# easyeda-schematic.net
KiCad netlist of a schematic drawn in EasyEDA
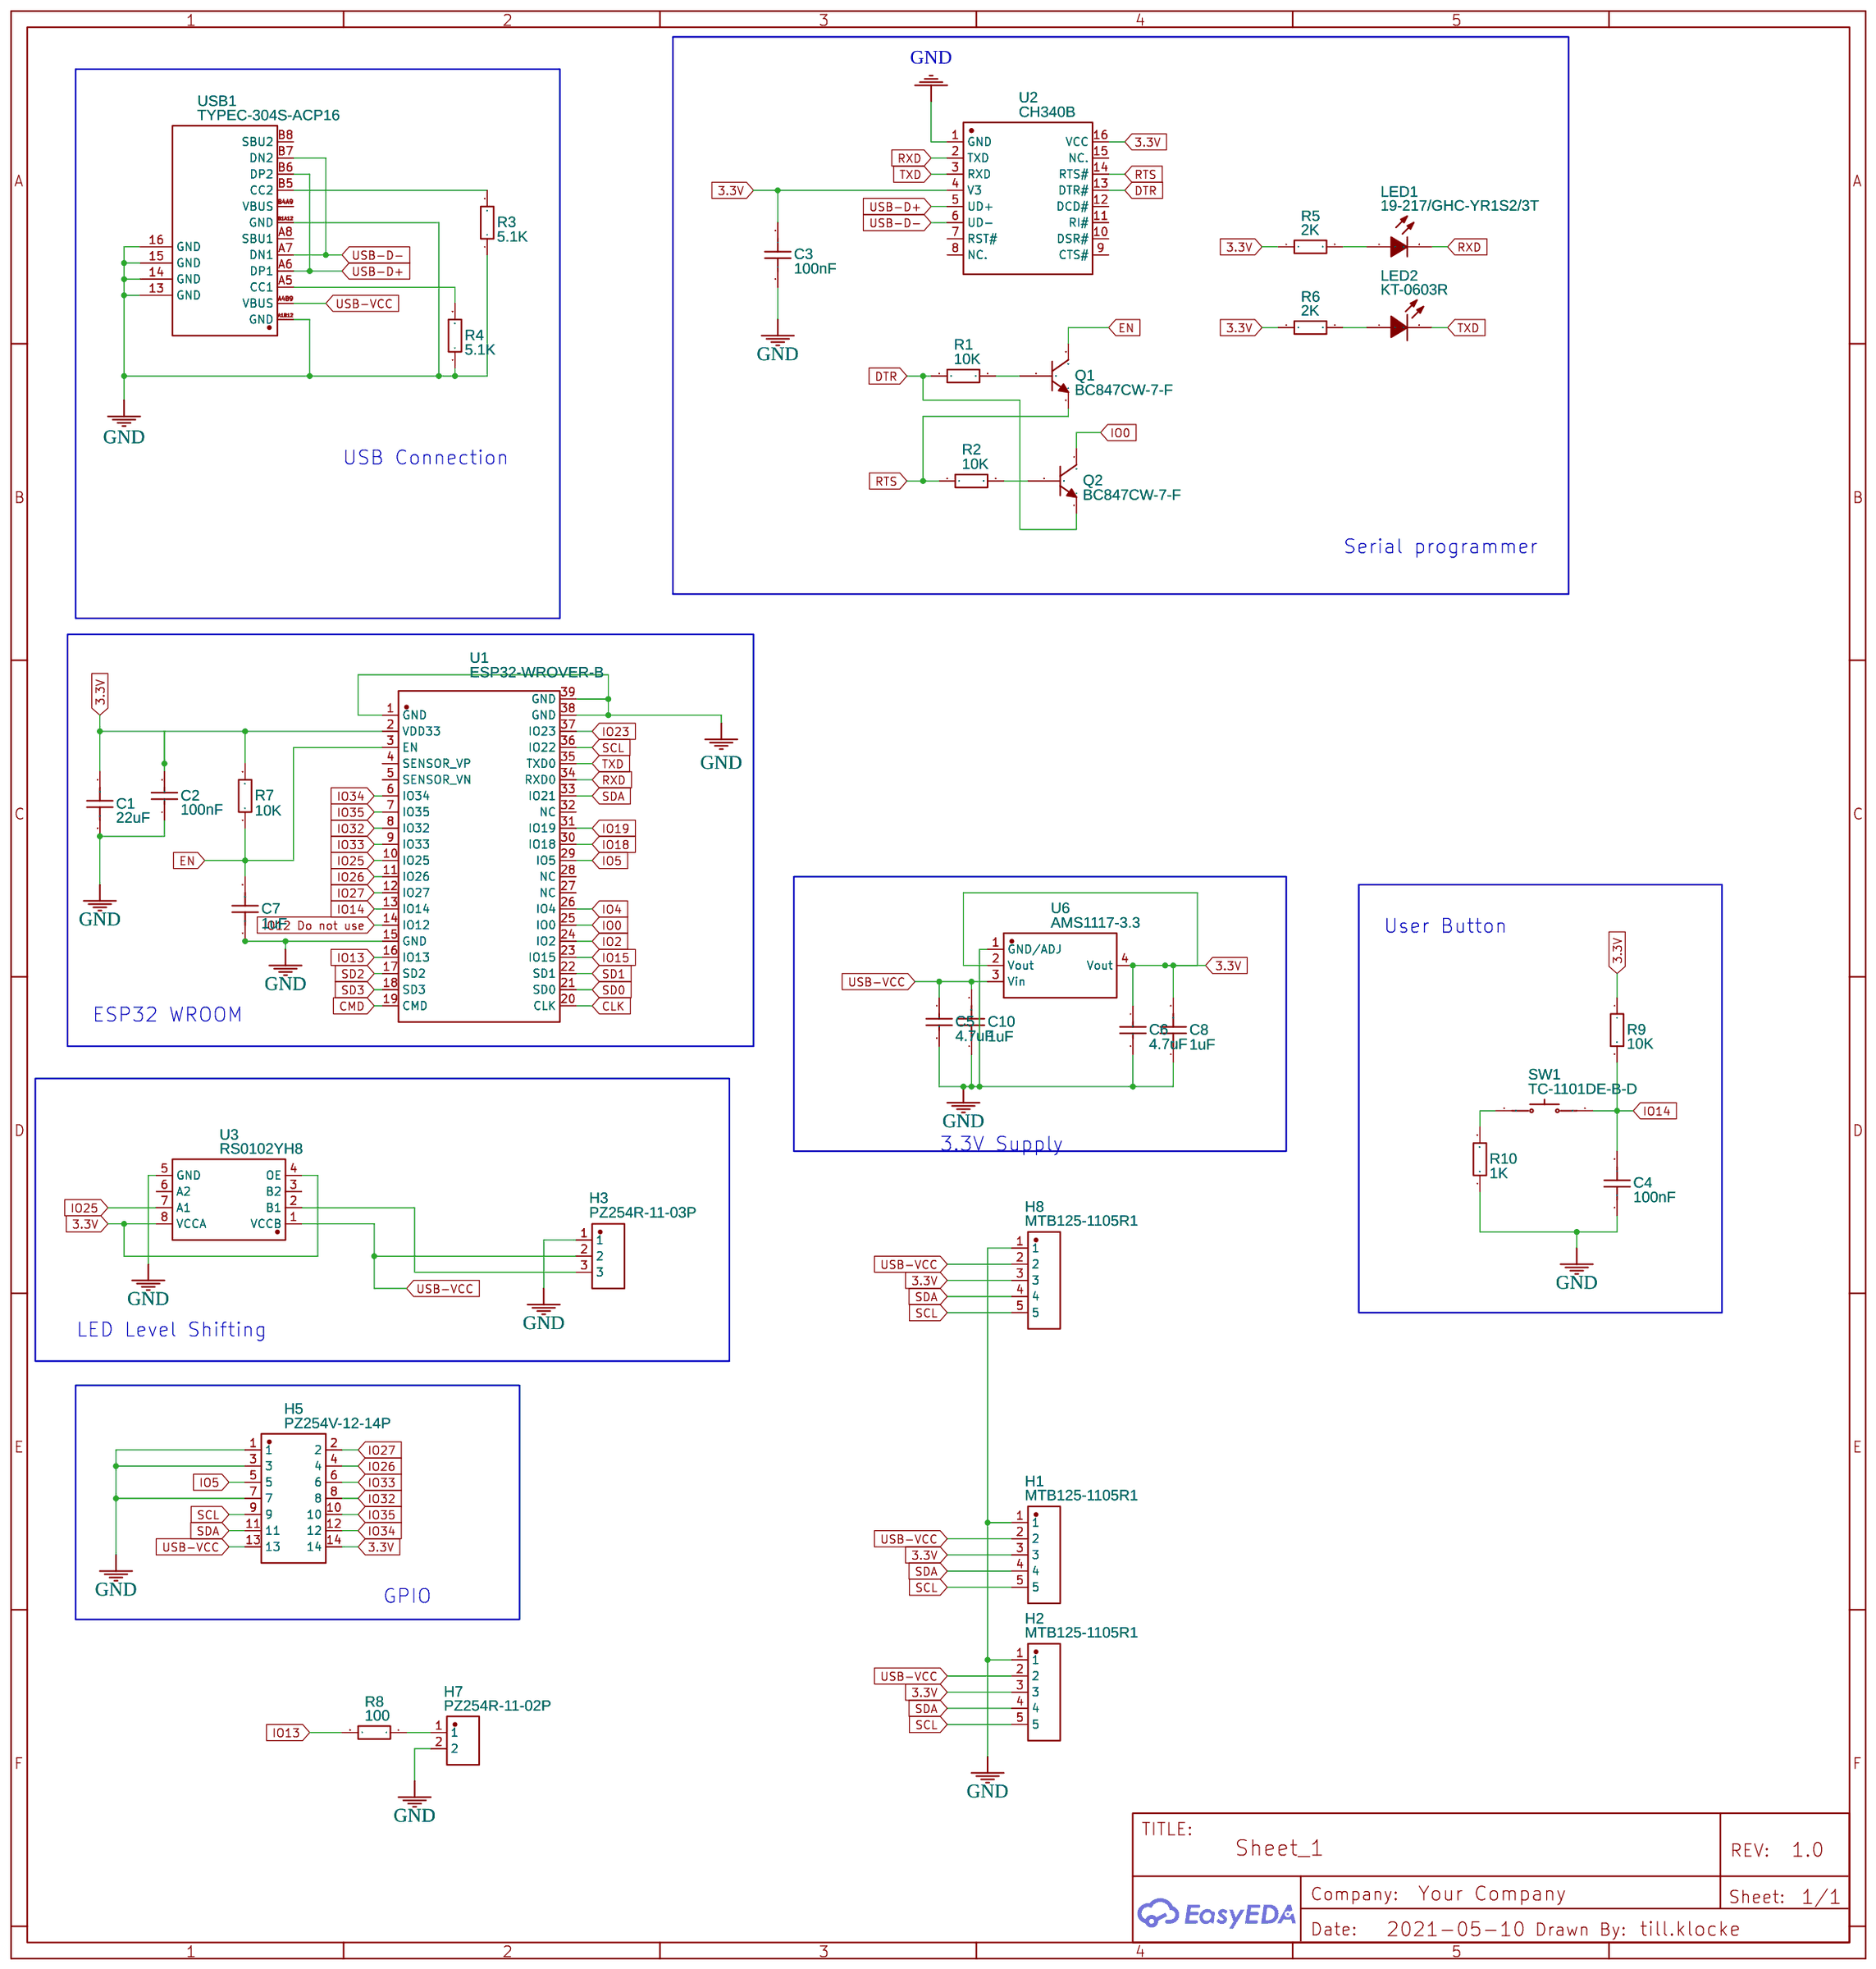
[diagram p0: schematic sheet]

(export (version "E")
  (design (tool "Eeschema 10.0.6"))
  (components
    (comp (ref "C1")
      (value "22uF")
      (fields
        (field (name "BOM_Manufacturer Part") "CL10A226MQ8NRNC")
        (field (name "BOM_Supplier Part") "C59461")
      )
      (libsource (lib "") (part "CL10A226MQ8NRNC"))
    )
    (comp (ref "C2")
      (value "100nF")
      (fields
        (field (name "BOM_Manufacturer Part") "CL05B104KO5NNNC")
        (field (name "BOM_Supplier Part") "C1525")
      )
      (libsource (lib "") (part "CL05B104KO5NNNC"))
    )
    (comp (ref "C3")
      (value "100nF")
      (fields
        (field (name "BOM_Manufacturer Part") "CC0603KRX7R9BB104")
        (field (name "BOM_Supplier Part") "C14663")
      )
      (libsource (lib "") (part "CC0603KRX7R9BB104"))
    )
    (comp (ref "C4")
      (value "100nF")
      (fields
        (field (name "BOM_Manufacturer Part") "CC0603KRX7R9BB104")
        (field (name "BOM_Supplier Part") "C14663")
      )
      (libsource (lib "") (part "CC0603KRX7R9BB104"))
    )
    (comp (ref "C5")
      (value "4.7uF")
      (fields
        (field (name "BOM_Manufacturer Part") "CL05A475MP5NRNC")
        (field (name "BOM_Supplier Part") "C23733")
      )
      (libsource (lib "") (part "CL05A475MP5NRNC"))
    )
    (comp (ref "C6")
      (value "4.7uF")
      (fields
        (field (name "BOM_Manufacturer Part") "CL05A475MP5NRNC")
        (field (name "BOM_Supplier Part") "C23733")
      )
      (libsource (lib "") (part "CL05A475MP5NRNC"))
    )
    (comp (ref "C7")
      (value "1uF")
      (fields
        (field (name "BOM_Manufacturer Part") "CL05A105KA5NQNC")
        (field (name "BOM_Supplier Part") "C52923")
      )
      (libsource (lib "") (part "CL05A105KA5NQNC"))
    )
    (comp (ref "C8")
      (value "1uF")
      (fields
        (field (name "BOM_Manufacturer Part") "CL05A105KA5NQNC")
        (field (name "BOM_Supplier Part") "C52923")
      )
      (libsource (lib "") (part "CL05A105KA5NQNC"))
    )
    (comp (ref "C10")
      (value "1uF")
      (fields
        (field (name "BOM_Manufacturer Part") "CL05A105KA5NQNC")
        (field (name "BOM_Supplier Part") "C52923")
      )
      (libsource (lib "") (part "CL05A105KA5NQNC"))
    )
    (comp (ref "H1")
      (value "MTB125-1105R1")
      (fields (field (name "BOM_Supplier Part") "C376123"))
      (libsource (lib "") (part "MTB125-1105R1"))
    )
    (comp (ref "H2")
      (value "MTB125-1105R1")
      (fields (field (name "BOM_Supplier Part") "C376123"))
      (libsource (lib "") (part "MTB125-1105R1"))
    )
    (comp (ref "H3")
      (value "PZ254R-11-03P")
      (fields (field (name "BOM_Supplier Part") "C492411"))
      (libsource (lib "") (part "PZ254R-11-03P"))
    )
    (comp (ref "H5")
      (value "PZ254V-12-14P")
      (fields (field (name "BOM_Supplier Part") "C492424"))
      (libsource (lib "") (part "PZ254V-12-14P"))
    )
    (comp (ref "H7")
      (value "PZ254R-11-02P")
      (fields (field (name "BOM_Supplier Part") "C492410"))
      (libsource (lib "") (part "PZ254R-11-02P"))
    )
    (comp (ref "H8")
      (value "MTB125-1105R1")
      (fields (field (name "BOM_Supplier Part") "C376123"))
      (libsource (lib "") (part "MTB125-1105R1"))
    )
    (comp (ref "LED1")
      (value "19-217/GHC-YR1S2/3T")
      (fields (field (name "BOM_Supplier Part") "C72043"))
      (libsource (lib "") (part "19-217/GHC-YR1S2/3T"))
    )
    (comp (ref "LED2")
      (value "KT-0603R")
      (fields (field (name "BOM_Supplier Part") "C2286"))
      (libsource (lib "") (part "KT-0603R"))
    )
    (comp (ref "Q1")
      (value "BC847CW-7-F")
      (fields (field (name "BOM_Supplier Part") "C151600"))
      (libsource (lib "") (part "BC847CW-7-F"))
    )
    (comp (ref "Q2")
      (value "BC847CW-7-F")
      (fields (field (name "BOM_Supplier Part") "C151600"))
      (libsource (lib "") (part "BC847CW-7-F"))
    )
    (comp (ref "R1")
      (value "10K")
      (fields
        (field (name "BOM_Manufacturer Part") "0402WGF1002TCE")
        (field (name "BOM_Supplier Part") "C25744")
      )
      (libsource (lib "") (part "0402WGF1002TCE"))
    )
    (comp (ref "R2")
      (value "10K")
      (fields
        (field (name "BOM_Manufacturer Part") "0402WGF1002TCE")
        (field (name "BOM_Supplier Part") "C25744")
      )
      (libsource (lib "") (part "0402WGF1002TCE"))
    )
    (comp (ref "R3")
      (value "5.1K")
      (fields
        (field (name "BOM_Manufacturer Part") "0805W8F5101T5E")
        (field (name "BOM_Supplier Part") "C27834")
      )
      (libsource (lib "") (part "0805W8F5101T5E"))
    )
    (comp (ref "R4")
      (value "5.1K")
      (fields
        (field (name "BOM_Manufacturer Part") "0805W8F5101T5E")
        (field (name "BOM_Supplier Part") "C27834")
      )
      (libsource (lib "") (part "0805W8F5101T5E"))
    )
    (comp (ref "R5")
      (value "2K")
      (fields
        (field (name "BOM_Manufacturer Part") "0402WGJ0202TCE")
        (field (name "BOM_Supplier Part") "C25552")
      )
      (libsource (lib "") (part "0402WGJ0202TCE"))
    )
    (comp (ref "R6")
      (value "2K")
      (fields
        (field (name "BOM_Manufacturer Part") "0402WGJ0202TCE")
        (field (name "BOM_Supplier Part") "C25552")
      )
      (libsource (lib "") (part "0402WGJ0202TCE"))
    )
    (comp (ref "R7")
      (value "10K")
      (fields
        (field (name "BOM_Manufacturer Part") "0402WGF1002TCE")
        (field (name "BOM_Supplier Part") "C25744")
      )
      (libsource (lib "") (part "0402WGF1002TCE_1"))
    )
    (comp (ref "R8")
      (value "100")
      (fields
        (field (name "BOM_Manufacturer Part") "RC0402FR-07100RL")
        (field (name "BOM_Supplier Part") "C106232")
      )
      (libsource (lib "") (part "RC0402FR-07100RL"))
    )
    (comp (ref "R9")
      (value "10K")
      (fields
        (field (name "BOM_Manufacturer Part") "0402WGF1002TCE")
        (field (name "BOM_Supplier Part") "C25744")
      )
      (libsource (lib "") (part "0402WGF1002TCE_2"))
    )
    (comp (ref "R10")
      (value "1K")
      (fields
        (field (name "BOM_Manufacturer Part") "0402WGF1001TCE")
        (field (name "BOM_Supplier Part") "C11702")
      )
      (libsource (lib "") (part "0402WGF1001TCE"))
    )
    (comp (ref "SW1")
      (value "TC-1101DE-B-D")
      (fields (field (name "BOM_Supplier Part") "C561494"))
      (libsource (lib "") (part "TC-1101DE-B-D"))
    )
    (comp (ref "U1")
      (value "ESP32-WROVER-B")
      (fields (field (name "BOM_Supplier Part") "C503591"))
      (libsource (lib "") (part "ESP32-WROVER-B"))
    )
    (comp (ref "U2")
      (value "CH340B")
      (fields (field (name "BOM_Supplier Part") "C81010"))
      (libsource (lib "") (part "CH340B"))
    )
    (comp (ref "U3")
      (value "RS0102YH8")
      (fields (field (name "BOM_Supplier Part") "C783414"))
      (libsource (lib "") (part "RS0102YH8"))
    )
    (comp (ref "U6")
      (value "AMS1117-3.3")
      (fields (field (name "BOM_Supplier Part") "C6186"))
      (libsource (lib "") (part "AMS1117-3.3"))
    )
    (comp (ref "USB1")
      (value "TYPEC-304S-ACP16")
      (fields (field (name "BOM_Supplier Part") "C720630"))
      (libsource (lib "") (part "TYPEC-304S-ACP16"))
    )
  )
  (nets
    (net (code "1") (name "3.3V") (class "Default")
      (node (ref "C1") (pin "1") (pinfunction "1_1") (pintype "unspecified"))
      (node (ref "C2") (pin "2") (pinfunction "2_2") (pintype "input"))
      (node (ref "C3") (pin "2") (pinfunction "2_2") (pintype "unspecified"))
      (node (ref "C6") (pin "1") (pinfunction "1_1") (pintype "input"))
      (node (ref "C8") (pin "2") (pinfunction "2_2") (pintype "unspecified"))
      (node (ref "H1") (pin "3") (pinfunction "3_3") (pintype "unspecified"))
      (node (ref "H2") (pin "3") (pinfunction "3_3") (pintype "unspecified"))
      (node (ref "H5") (pin "14") (pinfunction "14_14") (pintype "unspecified"))
      (node (ref "H8") (pin "3") (pinfunction "3_3") (pintype "unspecified"))
      (node (ref "R5") (pin "1") (pinfunction "1_1") (pintype "input"))
      (node (ref "R6") (pin "1") (pinfunction "1_1") (pintype "input"))
      (node (ref "R7") (pin "2") (pinfunction "2_2") (pintype "input"))
      (node (ref "R9") (pin "1") (pinfunction "1_1") (pintype "input"))
      (node (ref "U1") (pin "2") (pinfunction "VDD33_2") (pintype "unspecified"))
      (node (ref "U2") (pin "16") (pinfunction "VCC_16") (pintype "unspecified"))
      (node (ref "U2") (pin "4") (pinfunction "V3_4") (pintype "unspecified"))
      (node (ref "U3") (pin "4") (pinfunction "OE_4") (pintype "unspecified"))
      (node (ref "U3") (pin "8") (pinfunction "VCCA_8") (pintype "unspecified"))
      (node (ref "U6") (pin "2") (pinfunction "Vout_2") (pintype "unspecified"))
      (node (ref "U6") (pin "4") (pinfunction "Vout_4") (pintype "unspecified"))
    )
    (net (code "2") (name "CLK") (class "Default")
      (node (ref "U1") (pin "20") (pinfunction "CLK_20") (pintype "unspecified"))
    )
    (net (code "3") (name "CMD") (class "Default")
      (node (ref "U1") (pin "19") (pinfunction "CMD_19") (pintype "unspecified"))
    )
    (net (code "4") (name "DTR") (class "Default")
      (node (ref "Q2") (pin "2") (pinfunction "E_2") (pintype "unspecified"))
      (node (ref "R1") (pin "1") (pinfunction "1_1") (pintype "input"))
      (node (ref "U2") (pin "13") (pinfunction "DTR#_13") (pintype "unspecified"))
    )
    (net (code "5") (name "EN") (class "Default")
      (node (ref "C7") (pin "2") (pinfunction "2_2") (pintype "unspecified"))
      (node (ref "Q1") (pin "3") (pinfunction "C_3") (pintype "unspecified"))
      (node (ref "R7") (pin "1") (pinfunction "1_1") (pintype "input"))
      (node (ref "U1") (pin "3") (pinfunction "EN_3") (pintype "unspecified"))
    )
    (net (code "6") (name "GND") (class "Default")
      (node (ref "C1") (pin "2") (pinfunction "2_2") (pintype "unspecified"))
      (node (ref "C10") (pin "1") (pinfunction "1_1") (pintype "unspecified"))
      (node (ref "C2") (pin "1") (pinfunction "1_1") (pintype "input"))
      (node (ref "C3") (pin "1") (pinfunction "1_1") (pintype "unspecified"))
      (node (ref "C4") (pin "1") (pinfunction "1_1") (pintype "unspecified"))
      (node (ref "C5") (pin "2") (pinfunction "2_2") (pintype "input"))
      (node (ref "C6") (pin "2") (pinfunction "2_2") (pintype "input"))
      (node (ref "C7") (pin "1") (pinfunction "1_1") (pintype "unspecified"))
      (node (ref "C8") (pin "1") (pinfunction "1_1") (pintype "unspecified"))
      (node (ref "H1") (pin "1") (pinfunction "1_1") (pintype "unspecified"))
      (node (ref "H2") (pin "1") (pinfunction "1_1") (pintype "unspecified"))
      (node (ref "H3") (pin "1") (pinfunction "1_1") (pintype "unspecified"))
      (node (ref "H5") (pin "1") (pinfunction "1_1") (pintype "unspecified"))
      (node (ref "H5") (pin "3") (pinfunction "3_3") (pintype "unspecified"))
      (node (ref "H5") (pin "7") (pinfunction "7_7") (pintype "unspecified"))
      (node (ref "H7") (pin "2") (pinfunction "2_2") (pintype "unspecified"))
      (node (ref "H8") (pin "1") (pinfunction "1_1") (pintype "unspecified"))
      (node (ref "R10") (pin "1") (pinfunction "1_1") (pintype "input"))
      (node (ref "R3") (pin "1") (pinfunction "1_1") (pintype "input"))
      (node (ref "R4") (pin "1") (pinfunction "1_1") (pintype "input"))
      (node (ref "U1") (pin "1") (pinfunction "GND_1") (pintype "unspecified"))
      (node (ref "U1") (pin "15") (pinfunction "GND_15") (pintype "unspecified"))
      (node (ref "U1") (pin "38") (pinfunction "GND_38") (pintype "unspecified"))
      (node (ref "U1") (pin "39") (pinfunction "GND_39") (pintype "unspecified"))
      (node (ref "U2") (pin "1") (pinfunction "GND_1") (pintype "unspecified"))
      (node (ref "U3") (pin "5") (pinfunction "GND_5") (pintype "unspecified"))
      (node (ref "U6") (pin "1") (pinfunction "GND/ADJ_1") (pintype "unspecified"))
      (node (ref "USB1") (pin "13") (pinfunction "GND_13") (pintype "unspecified"))
      (node (ref "USB1") (pin "14") (pinfunction "GND_14") (pintype "unspecified"))
      (node (ref "USB1") (pin "15") (pinfunction "GND_15") (pintype "unspecified"))
      (node (ref "USB1") (pin "16") (pinfunction "GND_16") (pintype "unspecified"))
      (node (ref "USB1") (pin "A1B12") (pinfunction "GND_A1B12") (pintype "unspecified"))
      (node (ref "USB1") (pin "B1A12") (pinfunction "GND_B1A12") (pintype "unspecified"))
    )
    (net (code "7") (name "IO0") (class "Default")
      (node (ref "Q2") (pin "3") (pinfunction "C_3") (pintype "unspecified"))
      (node (ref "U1") (pin "25") (pinfunction "IO0_25") (pintype "unspecified"))
    )
    (net (code "8") (name "IO2") (class "Default")
      (node (ref "U1") (pin "24") (pinfunction "IO2_24") (pintype "unspecified"))
    )
    (net (code "9") (name "IO4") (class "Default")
      (node (ref "U1") (pin "26") (pinfunction "IO4_26") (pintype "unspecified"))
    )
    (net (code "10") (name "IO5") (class "Default")
      (node (ref "H5") (pin "5") (pinfunction "5_5") (pintype "unspecified"))
      (node (ref "U1") (pin "29") (pinfunction "IO5_29") (pintype "unspecified"))
    )
    (net (code "11") (name "IO12 Do not use") (class "Default")
      (node (ref "U1") (pin "14") (pinfunction "IO12_14") (pintype "unspecified"))
    )
    (net (code "12") (name "IO13") (class "Default")
      (node (ref "R8") (pin "2") (pinfunction "2_2") (pintype "input"))
      (node (ref "U1") (pin "16") (pinfunction "IO13_16") (pintype "unspecified"))
    )
    (net (code "13") (name "IO14") (class "Default")
      (node (ref "C4") (pin "2") (pinfunction "2_2") (pintype "unspecified"))
      (node (ref "R9") (pin "2") (pinfunction "2_2") (pintype "input"))
      (node (ref "SW1") (pin "2") (pinfunction "2_2") (pintype "input"))
      (node (ref "U1") (pin "13") (pinfunction "IO14_13") (pintype "unspecified"))
    )
    (net (code "14") (name "IO15") (class "Default")
      (node (ref "U1") (pin "23") (pinfunction "IO15_23") (pintype "unspecified"))
    )
    (net (code "15") (name "IO18") (class "Default")
      (node (ref "U1") (pin "30") (pinfunction "IO18_30") (pintype "unspecified"))
    )
    (net (code "16") (name "IO19") (class "Default")
      (node (ref "U1") (pin "31") (pinfunction "IO19_31") (pintype "unspecified"))
    )
    (net (code "17") (name "IO23") (class "Default")
      (node (ref "U1") (pin "37") (pinfunction "IO23_37") (pintype "unspecified"))
    )
    (net (code "18") (name "IO25") (class "Default")
      (node (ref "U1") (pin "10") (pinfunction "IO25_10") (pintype "unspecified"))
      (node (ref "U3") (pin "7") (pinfunction "A1_7") (pintype "unspecified"))
    )
    (net (code "19") (name "IO26") (class "Default")
      (node (ref "H5") (pin "4") (pinfunction "4_4") (pintype "unspecified"))
      (node (ref "U1") (pin "11") (pinfunction "IO26_11") (pintype "unspecified"))
    )
    (net (code "20") (name "IO27") (class "Default")
      (node (ref "H5") (pin "2") (pinfunction "2_2") (pintype "unspecified"))
      (node (ref "U1") (pin "12") (pinfunction "IO27_12") (pintype "unspecified"))
    )
    (net (code "21") (name "IO32") (class "Default")
      (node (ref "H5") (pin "8") (pinfunction "8_8") (pintype "unspecified"))
      (node (ref "U1") (pin "8") (pinfunction "IO32_8") (pintype "unspecified"))
    )
    (net (code "22") (name "IO33") (class "Default")
      (node (ref "H5") (pin "6") (pinfunction "6_6") (pintype "unspecified"))
      (node (ref "U1") (pin "9") (pinfunction "IO33_9") (pintype "unspecified"))
    )
    (net (code "23") (name "IO34") (class "Default")
      (node (ref "H5") (pin "12") (pinfunction "12_12") (pintype "unspecified"))
      (node (ref "U1") (pin "6") (pinfunction "IO34_6") (pintype "unspecified"))
    )
    (net (code "24") (name "IO35") (class "Default")
      (node (ref "H5") (pin "10") (pinfunction "10_10") (pintype "unspecified"))
      (node (ref "U1") (pin "7") (pinfunction "IO35_7") (pintype "unspecified"))
    )
    (net (code "25") (name "Net-(H7-Pad1)") (class "Default")
      (node (ref "H7") (pin "1") (pinfunction "1_1") (pintype "unspecified"))
      (node (ref "R8") (pin "1") (pinfunction "1_1") (pintype "input"))
    )
    (net (code "26") (name "Net-(LED1-A)") (class "Default")
      (node (ref "LED1") (pin "1") (pinfunction "A_1") (pintype "input"))
      (node (ref "R5") (pin "2") (pinfunction "2_2") (pintype "input"))
    )
    (net (code "27") (name "Net-(LED2-A)") (class "Default")
      (node (ref "LED2") (pin "1") (pinfunction "A_1") (pintype "unspecified"))
      (node (ref "R6") (pin "2") (pinfunction "2_2") (pintype "input"))
    )
    (net (code "28") (name "Net-(Q1-B)") (class "Default")
      (node (ref "Q1") (pin "1") (pinfunction "B_1") (pintype "unspecified"))
      (node (ref "R1") (pin "2") (pinfunction "2_2") (pintype "input"))
    )
    (net (code "29") (name "Net-(Q2-B)") (class "Default")
      (node (ref "Q2") (pin "1") (pinfunction "B_1") (pintype "unspecified"))
      (node (ref "R2") (pin "2") (pinfunction "2_2") (pintype "input"))
    )
    (net (code "30") (name "Net-(R10-Pad2)") (class "Default")
      (node (ref "R10") (pin "2") (pinfunction "2_2") (pintype "input"))
      (node (ref "SW1") (pin "1") (pinfunction "1_1") (pintype "input"))
    )
    (net (code "31") (name "Net-(U3-B1)") (class "Default")
      (node (ref "H3") (pin "3") (pinfunction "3_3") (pintype "unspecified"))
      (node (ref "U3") (pin "2") (pinfunction "B1_2") (pintype "unspecified"))
    )
    (net (code "32") (name "Net-(USB1-CC1)") (class "Default")
      (node (ref "R4") (pin "2") (pinfunction "2_2") (pintype "input"))
      (node (ref "USB1") (pin "A5") (pinfunction "CC1_A5") (pintype "unspecified"))
    )
    (net (code "33") (name "Net-(USB1-CC2)") (class "Default")
      (node (ref "R3") (pin "2") (pinfunction "2_2") (pintype "input"))
      (node (ref "USB1") (pin "B5") (pinfunction "CC2_B5") (pintype "unspecified"))
    )
    (net (code "34") (name "RTS") (class "Default")
      (node (ref "Q1") (pin "2") (pinfunction "E_2") (pintype "unspecified"))
      (node (ref "R2") (pin "1") (pinfunction "1_1") (pintype "input"))
      (node (ref "U2") (pin "14") (pinfunction "RTS#_14") (pintype "unspecified"))
    )
    (net (code "35") (name "RXD") (class "Default")
      (node (ref "LED1") (pin "2") (pinfunction "C_2") (pintype "input"))
      (node (ref "U1") (pin "34") (pinfunction "RXD0_34") (pintype "unspecified"))
      (node (ref "U2") (pin "2") (pinfunction "TXD_2") (pintype "unspecified"))
    )
    (net (code "36") (name "SCL") (class "Default")
      (node (ref "H1") (pin "5") (pinfunction "5_5") (pintype "unspecified"))
      (node (ref "H2") (pin "5") (pinfunction "5_5") (pintype "unspecified"))
      (node (ref "H5") (pin "9") (pinfunction "9_9") (pintype "unspecified"))
      (node (ref "H8") (pin "5") (pinfunction "5_5") (pintype "unspecified"))
      (node (ref "U1") (pin "36") (pinfunction "IO22_36") (pintype "unspecified"))
    )
    (net (code "37") (name "SD0") (class "Default")
      (node (ref "U1") (pin "21") (pinfunction "SD0_21") (pintype "unspecified"))
    )
    (net (code "38") (name "SD1") (class "Default")
      (node (ref "U1") (pin "22") (pinfunction "SD1_22") (pintype "unspecified"))
    )
    (net (code "39") (name "SD2") (class "Default")
      (node (ref "U1") (pin "17") (pinfunction "SD2_17") (pintype "unspecified"))
    )
    (net (code "40") (name "SD3") (class "Default")
      (node (ref "U1") (pin "18") (pinfunction "SD3_18") (pintype "unspecified"))
    )
    (net (code "41") (name "SDA") (class "Default")
      (node (ref "H1") (pin "4") (pinfunction "4_4") (pintype "unspecified"))
      (node (ref "H2") (pin "4") (pinfunction "4_4") (pintype "unspecified"))
      (node (ref "H5") (pin "11") (pinfunction "11_11") (pintype "unspecified"))
      (node (ref "H8") (pin "4") (pinfunction "4_4") (pintype "unspecified"))
      (node (ref "U1") (pin "33") (pinfunction "IO21_33") (pintype "unspecified"))
    )
    (net (code "42") (name "TXD") (class "Default")
      (node (ref "LED2") (pin "2") (pinfunction "K_2") (pintype "unspecified"))
      (node (ref "U1") (pin "35") (pinfunction "TXD0_35") (pintype "unspecified"))
      (node (ref "U2") (pin "3") (pinfunction "RXD_3") (pintype "unspecified"))
    )
    (net (code "43") (name "USB-D+") (class "Default")
      (node (ref "U2") (pin "5") (pinfunction "UD+_5") (pintype "unspecified"))
      (node (ref "USB1") (pin "A6") (pinfunction "DP1_A6") (pintype "unspecified"))
      (node (ref "USB1") (pin "B6") (pinfunction "DP2_B6") (pintype "unspecified"))
    )
    (net (code "44") (name "USB-D-") (class "Default")
      (node (ref "U2") (pin "6") (pinfunction "UD-_6") (pintype "unspecified"))
      (node (ref "USB1") (pin "A7") (pinfunction "DN1_A7") (pintype "unspecified"))
      (node (ref "USB1") (pin "B7") (pinfunction "DN2_B7") (pintype "unspecified"))
    )
    (net (code "45") (name "USB-VCC") (class "Default")
      (node (ref "C10") (pin "2") (pinfunction "2_2") (pintype "unspecified"))
      (node (ref "C5") (pin "1") (pinfunction "1_1") (pintype "input"))
      (node (ref "H1") (pin "2") (pinfunction "2_2") (pintype "unspecified"))
      (node (ref "H2") (pin "2") (pinfunction "2_2") (pintype "unspecified"))
      (node (ref "H3") (pin "2") (pinfunction "2_2") (pintype "unspecified"))
      (node (ref "H5") (pin "13") (pinfunction "13_13") (pintype "unspecified"))
      (node (ref "H8") (pin "2") (pinfunction "2_2") (pintype "unspecified"))
      (node (ref "U3") (pin "1") (pinfunction "VCCB_1") (pintype "unspecified"))
      (node (ref "U6") (pin "3") (pinfunction "Vin_3") (pintype "unspecified"))
      (node (ref "USB1") (pin "A4B9") (pinfunction "VBUS_A4B9") (pintype "unspecified"))
    )
    (net (code "46") (name "unconnected-(U1-NC-Pad27)") (class "Default")
      (node (ref "U1") (pin "27") (pinfunction "NC_27") (pintype "unspecified"))
    )
    (net (code "47") (name "unconnected-(U1-NC-Pad28)") (class "Default")
      (node (ref "U1") (pin "28") (pinfunction "NC_28") (pintype "unspecified"))
    )
    (net (code "48") (name "unconnected-(U1-NC-Pad32)") (class "Default")
      (node (ref "U1") (pin "32") (pinfunction "NC_32") (pintype "unspecified"))
    )
    (net (code "49") (name "unconnected-(U1-SENSOR_VN-Pad5)") (class "Default")
      (node (ref "U1") (pin "5") (pinfunction "SENSOR_VN_5") (pintype "unspecified"))
    )
    (net (code "50") (name "unconnected-(U1-SENSOR_VP-Pad4)") (class "Default")
      (node (ref "U1") (pin "4") (pinfunction "SENSOR_VP_4") (pintype "unspecified"))
    )
    (net (code "51") (name "unconnected-(U2-CTS#-Pad9)") (class "Default")
      (node (ref "U2") (pin "9") (pinfunction "CTS#_9") (pintype "unspecified"))
    )
    (net (code "52") (name "unconnected-(U2-DCD#-Pad12)") (class "Default")
      (node (ref "U2") (pin "12") (pinfunction "DCD#_12") (pintype "unspecified"))
    )
    (net (code "53") (name "unconnected-(U2-DSR#-Pad10)") (class "Default")
      (node (ref "U2") (pin "10") (pinfunction "DSR#_10") (pintype "unspecified"))
    )
    (net (code "54") (name "unconnected-(U2-NC.-Pad8)") (class "Default")
      (node (ref "U2") (pin "8") (pinfunction "NC._8") (pintype "unspecified"))
    )
    (net (code "55") (name "unconnected-(U2-NC.-Pad15)") (class "Default")
      (node (ref "U2") (pin "15") (pinfunction "NC._15") (pintype "unspecified"))
    )
    (net (code "56") (name "unconnected-(U2-RI#-Pad11)") (class "Default")
      (node (ref "U2") (pin "11") (pinfunction "RI#_11") (pintype "unspecified"))
    )
    (net (code "57") (name "unconnected-(U2-RST#-Pad7)") (class "Default")
      (node (ref "U2") (pin "7") (pinfunction "RST#_7") (pintype "unspecified"))
    )
    (net (code "58") (name "unconnected-(U3-A2-Pad6)") (class "Default")
      (node (ref "U3") (pin "6") (pinfunction "A2_6") (pintype "unspecified"))
    )
    (net (code "59") (name "unconnected-(U3-B2-Pad3)") (class "Default")
      (node (ref "U3") (pin "3") (pinfunction "B2_3") (pintype "unspecified"))
    )
    (net (code "60") (name "unconnected-(USB1-SBU1-PadA8)") (class "Default")
      (node (ref "USB1") (pin "A8") (pinfunction "SBU1_A8") (pintype "unspecified"))
    )
    (net (code "61") (name "unconnected-(USB1-SBU2-PadB8)") (class "Default")
      (node (ref "USB1") (pin "B8") (pinfunction "SBU2_B8") (pintype "unspecified"))
    )
    (net (code "62") (name "unconnected-(USB1-VBUS-PadB4A9)") (class "Default")
      (node (ref "USB1") (pin "B4A9") (pinfunction "VBUS_B4A9") (pintype "unspecified"))
    )
  )
)
